# general_Interface.net
KiCad netlist of a schematic drawn in Altium Designer
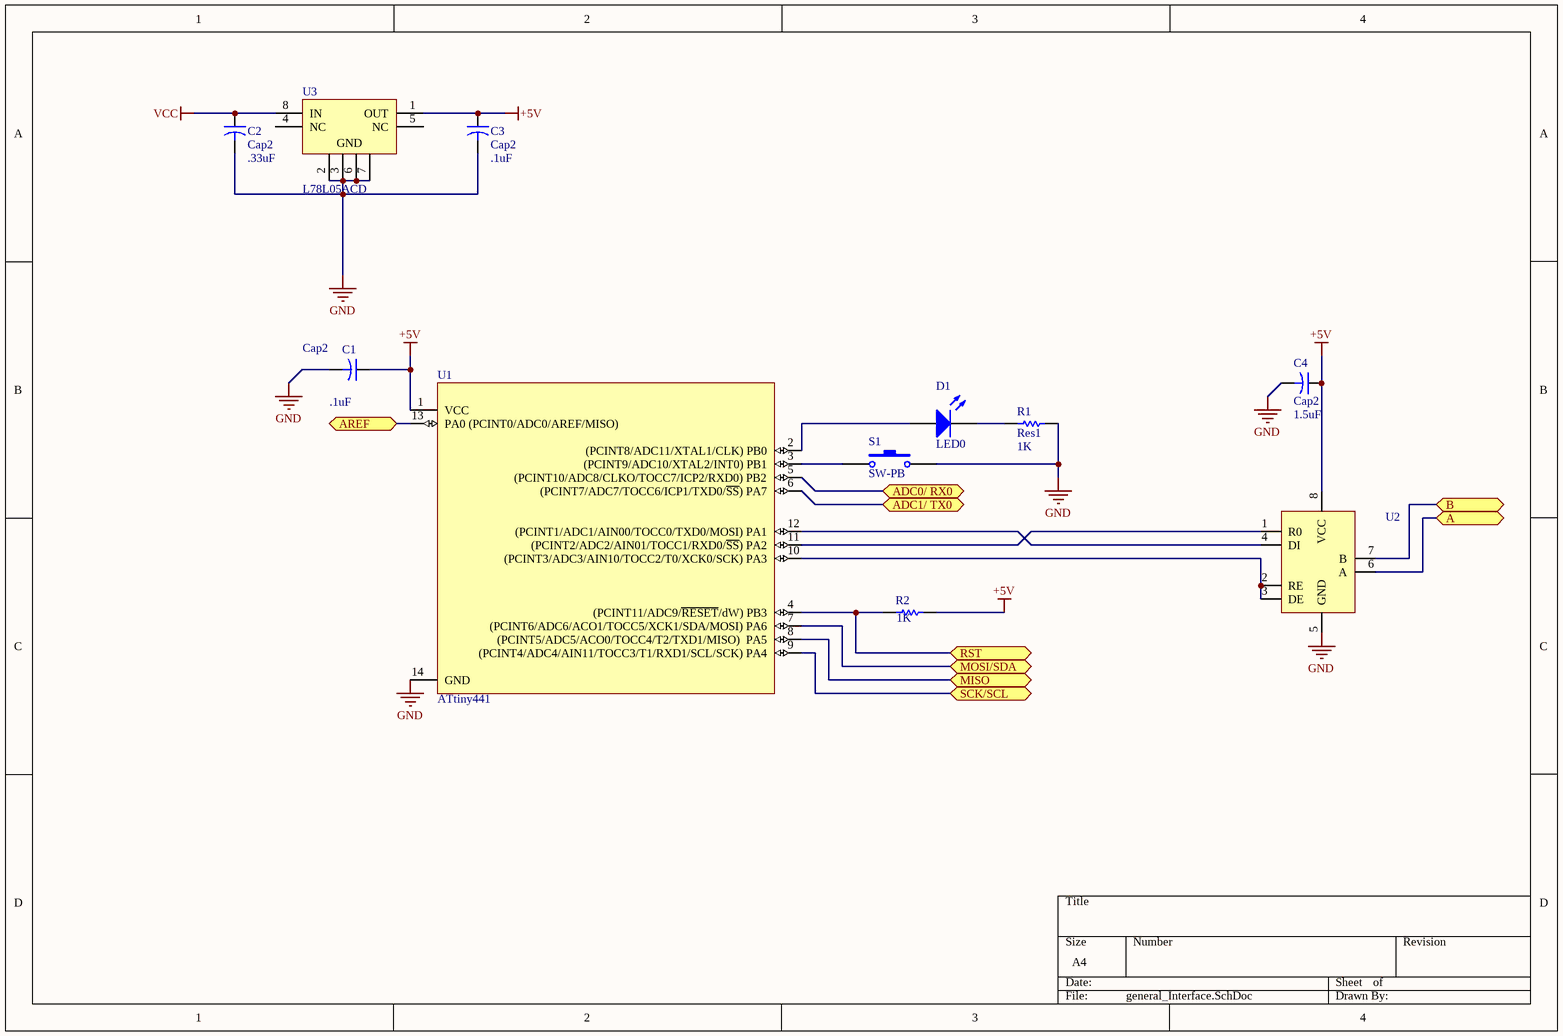
[diagram p0: general_Interface.SchDoc]

(export (version "E")
  (design (tool "Eeschema 10.0.6"))
  (components
    (comp (ref "C1")
      (value "Cap2")
      (footprint "6-0805_N")
      (description "Capacitor")
      (fields (field (name "ALTIUM_VALUE") ".1uF") (field (name "PUBLISHER") "Altium Limited"))
      (libsource (lib "Miscellaneous Devices") (part "Cap2"))
    )
    (comp (ref "C2")
      (value "Cap2")
      (footprint "6-0805_N")
      (description "Capacitor")
      (fields (field (name "ALTIUM_VALUE") ".33uF") (field (name "PUBLISHER") "Altium Limited"))
      (libsource (lib "Miscellaneous Devices") (part "Cap2"))
    )
    (comp (ref "C3")
      (value "Cap2")
      (footprint "6-0805_N")
      (description "Capacitor")
      (fields (field (name "ALTIUM_VALUE") ".1uF") (field (name "PUBLISHER") "Altium Limited"))
      (libsource (lib "Miscellaneous Devices") (part "Cap2"))
    )
    (comp (ref "C4")
      (value "Cap2")
      (footprint "6-0805_N")
      (description "Capacitor")
      (fields (field (name "ALTIUM_VALUE") "1.5uF") (field (name "PUBLISHER") "Altium Limited"))
      (libsource (lib "Miscellaneous Devices") (part "Cap2"))
    )
    (comp (ref "D1")
      (value "LED0")
      (footprint "1608[0603]")
      (description "Typical INFRARED GaAs LED")
      (fields (field (name "PUBLISHER") "Altium Limited"))
      (libsource (lib "Miscellaneous Devices") (part "LED0"))
    )
    (comp (ref "R1")
      (value "Res1")
      (footprint "6-0805_N")
      (description "Resistor")
      (fields (field (name "ALTIUM_VALUE") "1K") (field (name "PUBLISHER") "Altium Limited"))
      (libsource (lib "Miscellaneous Devices") (part "Res1"))
    )
    (comp (ref "R2")
      (value "1K")
      (footprint "J1-0603")
      (description "Resistor")
      (fields (field (name "Comment") "Res1") (field (name "PUBLISHER") "Altium Limited"))
      (libsource (lib "Miscellaneous Devices") (part "Res1"))
    )
    (comp (ref "S1")
      (value "SW-PB")
      (footprint "ADTSM3")
      (description "Switch")
      (fields (field (name "PUBLISHER") "Altium Limited"))
      (libsource (lib "Miscellaneous Devices") (part "SW-PB"))
    )
    (comp (ref "U1") (value "ATtiny441") (footprint "6ST1_L") (libsource (lib "MABSS") (part "ATtiny441")))
    (comp (ref "U2") (value "SP485") (footprint "8S1_M") (libsource (lib "MABSS") (part "SP485")))
    (comp (ref "U3")
      (value "L78L05ACD")
      (footprint "8S1_N")
      (description "Positive Voltage Regulator")
      (fields (field (name "PUBLISHER") "Altium Limited"))
      (libsource (lib "ST Power Mgt Voltage Regulator") (part "L78L05ACD"))
    )
  )
  (nets
    (net (code "1") (name "+5V") (class "Default")
      (node (ref "C1") (pin "1") (pinfunction "1_1") (pintype "passive"))
      (node (ref "C3") (pin "1") (pinfunction "1_1") (pintype "passive"))
      (node (ref "C4") (pin "1") (pinfunction "1_1") (pintype "passive"))
      (node (ref "R2") (pin "2") (pinfunction "2_2") (pintype "passive"))
      (node (ref "U1") (pin "1") (pinfunction "VCC_1") (pintype "power_in"))
      (node (ref "U2") (pin "8") (pinfunction "VCC_8") (pintype "passive"))
      (node (ref "U3") (pin "1") (pinfunction "OUT_1") (pintype "power_in"))
    )
    (net (code "2") (name "/A") (class "Default")
      (node (ref "U2") (pin "6") (pinfunction "A_6") (pintype "passive"))
    )
    (net (code "3") (name "/ADC0{slash} RX0") (class "Default")
      (node (ref "U1") (pin "5") (pinfunction "(PCINT10/ADC8/CLKO/TOCC7/ICP2/RXD0)_PB2_5") (pintype "bidirectional"))
    )
    (net (code "4") (name "/ADC1{slash} TX0") (class "Default")
      (node (ref "U1") (pin "6") (pinfunction "(PCINT7/ADC7/TOCC6/ICP1/TXD0/~{SS})_PA7_6") (pintype "bidirectional"))
    )
    (net (code "5") (name "/AREF") (class "Default")
      (node (ref "U1") (pin "13") (pinfunction "PA0_(PCINT0/ADC0/AREF/MISO)_13") (pintype "bidirectional"))
    )
    (net (code "6") (name "/B") (class "Default")
      (node (ref "U2") (pin "7") (pinfunction "B_7") (pintype "passive"))
    )
    (net (code "7") (name "/MISO") (class "Default")
      (node (ref "U1") (pin "8") (pinfunction "(PCINT5/ADC5/ACO0/TOCC4/T2/TXD1/MISO)__PA5_8") (pintype "bidirectional"))
    )
    (net (code "8") (name "/MOSI{slash}SDA") (class "Default")
      (node (ref "U1") (pin "7") (pinfunction "(PCINT6/ADC6/ACO1/TOCC5/XCK1/SDA/MOSI)_PA6_7") (pintype "bidirectional"))
    )
    (net (code "9") (name "/RST") (class "Default")
      (node (ref "R2") (pin "1") (pinfunction "1_1") (pintype "passive"))
      (node (ref "U1") (pin "4") (pinfunction "(PCINT11/ADC9/~{RESET}/dW)_PB3_4") (pintype "bidirectional"))
    )
    (net (code "10") (name "/SCK{slash}SCL") (class "Default")
      (node (ref "U1") (pin "9") (pinfunction "(PCINT4/ADC4/AIN11/TOCC3/T1/RXD1/SCL/SCK)_PA4_9") (pintype "bidirectional"))
    )
    (net (code "11") (name "GND") (class "Default")
      (node (ref "C1") (pin "2") (pinfunction "2_2") (pintype "passive"))
      (node (ref "C2") (pin "2") (pinfunction "2_2") (pintype "passive"))
      (node (ref "C3") (pin "2") (pinfunction "2_2") (pintype "passive"))
      (node (ref "C4") (pin "2") (pinfunction "2_2") (pintype "passive"))
      (node (ref "R1") (pin "2") (pinfunction "2_2") (pintype "passive"))
      (node (ref "S1") (pin "2") (pinfunction "2_2") (pintype "passive"))
      (node (ref "U1") (pin "14") (pinfunction "GND_14") (pintype "power_in"))
      (node (ref "U2") (pin "5") (pinfunction "GND_5") (pintype "passive"))
      (node (ref "U3") (pin "2") (pinfunction "GND_2") (pintype "power_in"))
      (node (ref "U3") (pin "3") (pinfunction "GND_3") (pintype "power_in"))
      (node (ref "U3") (pin "6") (pinfunction "GND_6") (pintype "power_in"))
      (node (ref "U3") (pin "7") (pinfunction "GND_7") (pintype "power_in"))
    )
    (net (code "12") (name "Net-(D1-A)") (class "Default")
      (node (ref "D1") (pin "1") (pinfunction "A_1") (pintype "passive"))
      (node (ref "U1") (pin "2") (pinfunction "(PCINT8/ADC11/XTAL1/CLK)_PB0_2") (pintype "bidirectional"))
    )
    (net (code "13") (name "Net-(D1-K)") (class "Default")
      (node (ref "D1") (pin "2") (pinfunction "K_2") (pintype "passive"))
      (node (ref "R1") (pin "1") (pinfunction "1_1") (pintype "passive"))
    )
    (net (code "14") (name "Net-(U1-(PCINT1{slash}ADC1{slash}AIN00{slash}TOCC0{slash}TXD0{slash}MOSI)_PA1)") (class "Default")
      (node (ref "U1") (pin "12") (pinfunction "(PCINT1/ADC1/AIN00/TOCC0/TXD0/MOSI)_PA1_12") (pintype "bidirectional"))
      (node (ref "U2") (pin "4") (pinfunction "DI_4") (pintype "passive"))
    )
    (net (code "15") (name "Net-(U1-(PCINT2{slash}ADC2{slash}AIN01{slash}TOCC1{slash}RXD0{slash}~{SS})_PA2)") (class "Default")
      (node (ref "U1") (pin "11") (pinfunction "(PCINT2/ADC2/AIN01/TOCC1/RXD0/~{SS})_PA2_11") (pintype "bidirectional"))
      (node (ref "U2") (pin "1") (pinfunction "R0_1") (pintype "passive"))
    )
    (net (code "16") (name "Net-(U1-(PCINT3{slash}ADC3{slash}AIN10{slash}TOCC2{slash}T0{slash}XCK0{slash}SCK)_PA3)") (class "Default")
      (node (ref "U1") (pin "10") (pinfunction "(PCINT3/ADC3/AIN10/TOCC2/T0/XCK0/SCK)_PA3_10") (pintype "bidirectional"))
      (node (ref "U2") (pin "2") (pinfunction "RE_2") (pintype "passive"))
      (node (ref "U2") (pin "3") (pinfunction "DE_3") (pintype "passive"))
    )
    (net (code "17") (name "Net-(U1-(PCINT9{slash}ADC10{slash}XTAL2{slash}INT0)_PB1)") (class "Default")
      (node (ref "S1") (pin "1") (pinfunction "1_1") (pintype "passive"))
      (node (ref "U1") (pin "3") (pinfunction "(PCINT9/ADC10/XTAL2/INT0)_PB1_3") (pintype "bidirectional"))
    )
    (net (code "18") (name "VCC") (class "Default")
      (node (ref "C2") (pin "1") (pinfunction "1_1") (pintype "passive"))
      (node (ref "U3") (pin "8") (pinfunction "IN_8") (pintype "power_in"))
    )
    (net (code "19") (name "unconnected-(U3-NC-Pad4)") (class "Default")
      (node (ref "U3") (pin "4") (pinfunction "NC_4") (pintype "passive"))
    )
    (net (code "20") (name "unconnected-(U3-NC-Pad5)") (class "Default")
      (node (ref "U3") (pin "5") (pinfunction "NC_5") (pintype "passive"))
    )
  )
)
